# Hplc103.net
KiCad netlist of a schematic drawn in Altium Designer
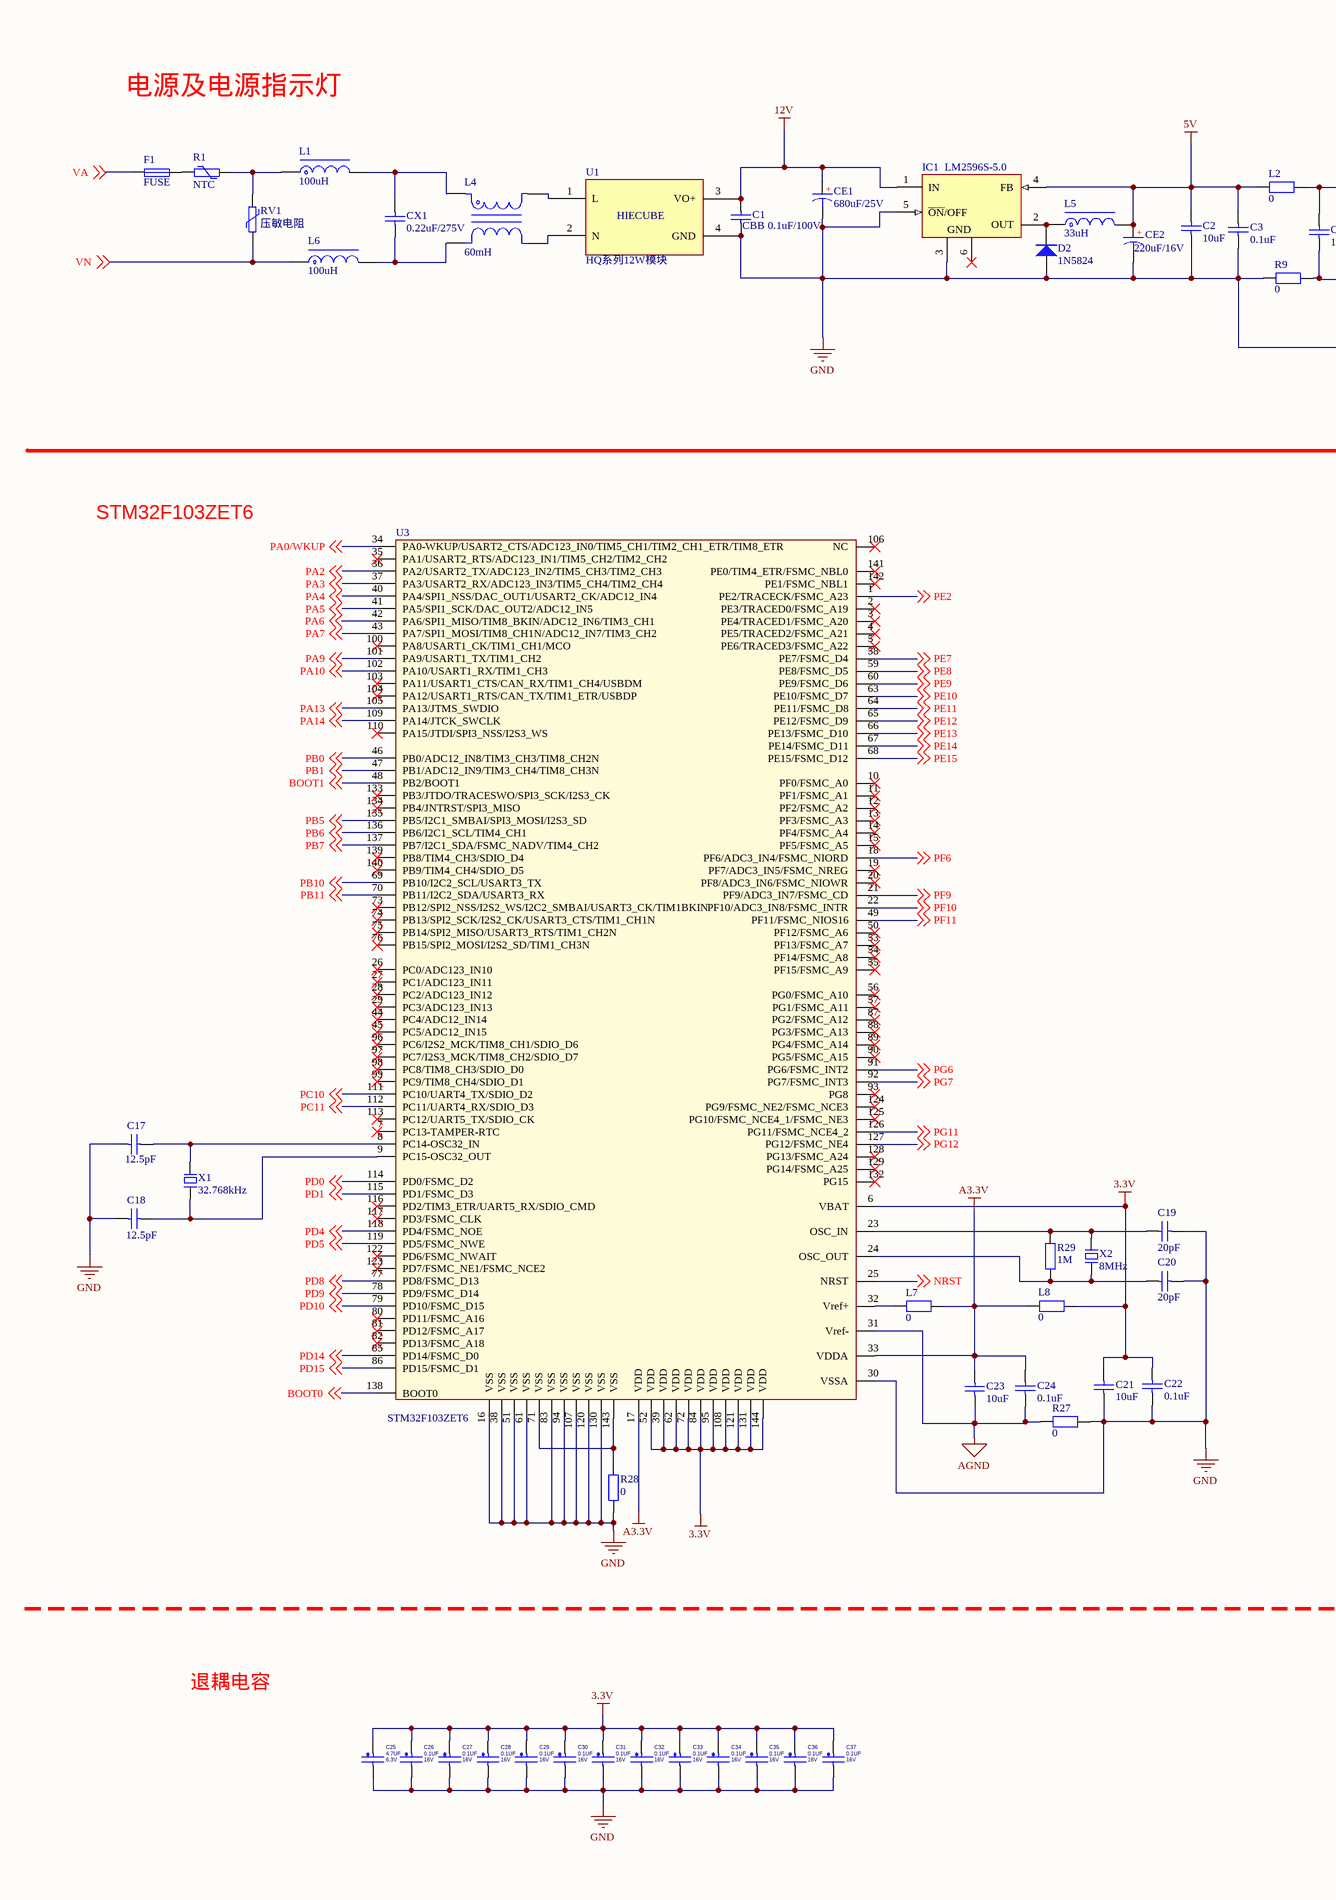
[diagram p0: Hplc103.SchDoc, left]
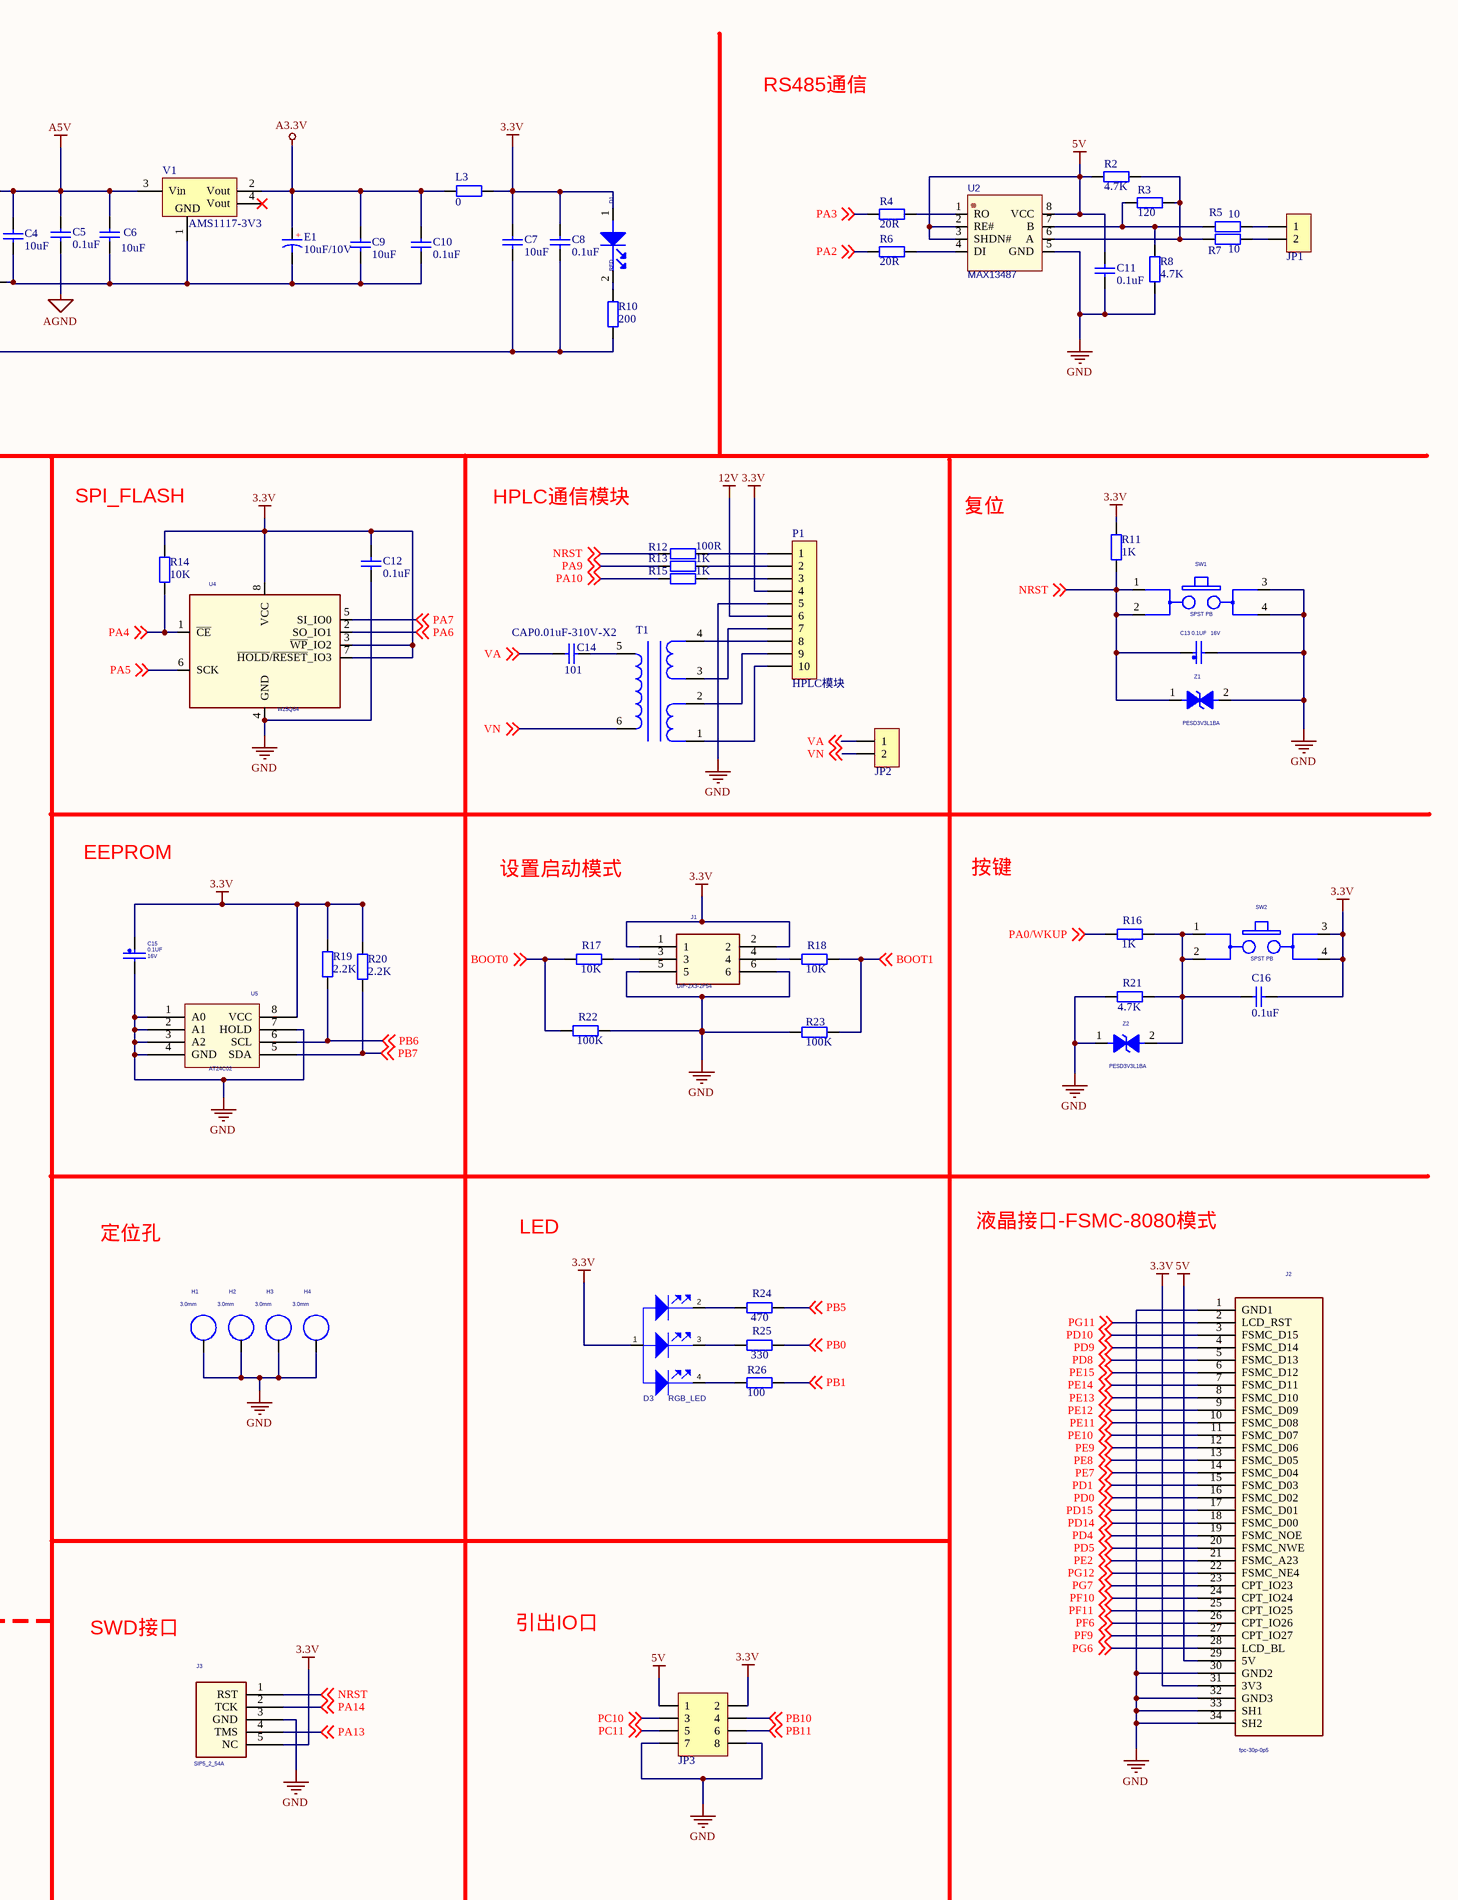
[diagram p1: Hplc103.SchDoc, right]

(export (version "E")
  (design (tool "Eeschema 10.0.6"))
  (components
    (comp (ref "C1")
      (value "CBB 0.1uF/100V")
      (footprint "CBB 5*6.3*3")
      (description "CBB电容")
      (libsource (lib "0.1 - 电阻-电容-电感-电位器") (part "CBB"))
    )
    (comp (ref "C2")
      (value "10uF")
      (footprint "C0805_M")
      (description "贴片电容")
      (libsource (lib "0.1 - 电阻-电容-电感-电位器") (part "C"))
    )
    (comp (ref "C3")
      (value "0.1uF")
      (footprint "C0805_M")
      (description "贴片电容")
      (libsource (lib "0.1 - 电阻-电容-电感-电位器") (part "C"))
    )
    (comp (ref "C4")
      (value "10uF")
      (footprint "C0805_M")
      (description "贴片电容")
      (libsource (lib "0.1 - 电阻-电容-电感-电位器") (part "C"))
    )
    (comp (ref "C5")
      (value "0.1uF")
      (footprint "C0805_M")
      (description "贴片电容")
      (libsource (lib "0.1 - 电阻-电容-电感-电位器") (part "C"))
    )
    (comp (ref "C6")
      (value "10uF")
      (footprint "C0805_M")
      (description "贴片电容")
      (libsource (lib "0.1 - 电阻-电容-电感-电位器") (part "C"))
    )
    (comp (ref "C7")
      (value "10uF")
      (footprint "C0805_M")
      (description "贴片电容")
      (libsource (lib "0.1 - 电阻-电容-电感-电位器") (part "C"))
    )
    (comp (ref "C8")
      (value "0.1uF")
      (footprint "C0805_M")
      (description "贴片电容")
      (libsource (lib "0.1 - 电阻-电容-电感-电位器") (part "C"))
    )
    (comp (ref "C9")
      (value "10uF")
      (footprint "C0805_M")
      (description "贴片电容")
      (libsource (lib "0.1 - 电阻-电容-电感-电位器") (part "C"))
    )
    (comp (ref "C10")
      (value "0.1uF")
      (footprint "C0805_M")
      (description "贴片电容")
      (libsource (lib "0.1 - 电阻-电容-电感-电位器") (part "C"))
    )
    (comp (ref "C11")
      (value "0.1uF")
      (footprint "C0805_M")
      (description "贴片电容")
      (libsource (lib "0.1 - 电阻-电容-电感-电位器") (part "C"))
    )
    (comp (ref "C12")
      (value "0.1uF")
      (footprint "C0805_M")
      (description "贴片电容")
      (libsource (lib "0.1 - 电阻-电容-电感-电位器") (part "C"))
    )
    (comp (ref "C13")
      (value "0.1UF")
      (description "CAP CER 22UF 6.3V 20% X5R 0603")
      (fields
        (field (name "TOLERANCE") "20%")
        (field (name "VOLTAGE") "6.3V")
        (field (name "VOLTAGE RATING") "16V")
      )
      (libsource (lib "Hplc103") (part "CAP_NP"))
    )
    (comp (ref "C14")
      (value "101")
      (footprint "CY 7.5*12*5")
      (fields (field (name "ALTIUM_UNNAMED_1") "CAP0.01uF-310V-X2"))
      (libsource (lib "Schlib1") (part "电容"))
    )
    (comp (ref "C15")
      (value "0.1UF")
      (description "CAP CER 22UF 6.3V 20% X5R 0402")
      (fields
        (field (name "TOLERANCE") "20%")
        (field (name "VOLTAGE") "6.3V")
        (field (name "VOLTAGE RATING") "16V")
      )
      (libsource (lib "Hplc103") (part "CAP_NP"))
    )
    (comp (ref "C16")
      (value "0.1uF")
      (footprint "C0805_M")
      (description "贴片电容")
      (libsource (lib "0.1 - 电阻-电容-电感-电位器") (part "C"))
    )
    (comp (ref "C17")
      (value "12.5pF")
      (footprint "C0805_M")
      (description "贴片电容")
      (libsource (lib "0.1 - 电阻-电容-电感-电位器") (part "C"))
    )
    (comp (ref "C18")
      (value "12.5pF")
      (footprint "C0805_M")
      (description "贴片电容")
      (libsource (lib "0.1 - 电阻-电容-电感-电位器") (part "C"))
    )
    (comp (ref "C19")
      (value "20pF")
      (footprint "C0805_M")
      (description "贴片电容")
      (libsource (lib "0.1 - 电阻-电容-电感-电位器") (part "C"))
    )
    (comp (ref "C20")
      (value "20pF")
      (footprint "C0805_M")
      (description "贴片电容")
      (libsource (lib "0.1 - 电阻-电容-电感-电位器") (part "C"))
    )
    (comp (ref "C21")
      (value "10uF")
      (footprint "C0805_M")
      (description "贴片电容")
      (libsource (lib "0.1 - 电阻-电容-电感-电位器") (part "C"))
    )
    (comp (ref "C22")
      (value "0.1uF")
      (footprint "C0805_M")
      (description "贴片电容")
      (libsource (lib "0.1 - 电阻-电容-电感-电位器") (part "C"))
    )
    (comp (ref "C23")
      (value "10uF")
      (footprint "C0805_M")
      (description "贴片电容")
      (libsource (lib "0.1 - 电阻-电容-电感-电位器") (part "C"))
    )
    (comp (ref "C24")
      (value "0.1uF")
      (footprint "C0805_M")
      (description "贴片电容")
      (libsource (lib "0.1 - 电阻-电容-电感-电位器") (part "C"))
    )
    (comp (ref "C25")
      (value "4.7UF")
      (footprint "C0603")
      (description "CAP CER 22UF 6.3V 20% X5R 0603")
      (fields
        (field (name "TOLERANCE") "20%")
        (field (name "VOLTAGE") "6.3V")
        (field (name "VOLTAGE RATING") "6.3V")
      )
      (libsource (lib "Hplc103") (part "CAP_NP"))
    )
    (comp (ref "C26")
      (value "0.1UF")
      (description "CAP CER 22UF 6.3V 20% X5R 0603")
      (fields
        (field (name "TOLERANCE") "20%")
        (field (name "VOLTAGE") "6.3V")
        (field (name "VOLTAGE RATING") "16V")
      )
      (libsource (lib "Hplc103") (part "CAP_NP"))
    )
    (comp (ref "C27")
      (value "0.1UF")
      (description "CAP CER 22UF 6.3V 20% X5R 0603")
      (fields
        (field (name "TOLERANCE") "20%")
        (field (name "VOLTAGE") "6.3V")
        (field (name "VOLTAGE RATING") "16V")
      )
      (libsource (lib "Hplc103") (part "CAP_NP"))
    )
    (comp (ref "C28")
      (value "0.1UF")
      (description "CAP CER 22UF 6.3V 20% X5R 0603")
      (fields
        (field (name "TOLERANCE") "20%")
        (field (name "VOLTAGE") "6.3V")
        (field (name "VOLTAGE RATING") "16V")
      )
      (libsource (lib "Hplc103") (part "CAP_NP"))
    )
    (comp (ref "C29")
      (value "0.1UF")
      (description "CAP CER 22UF 6.3V 20% X5R 0603")
      (fields
        (field (name "TOLERANCE") "20%")
        (field (name "VOLTAGE") "6.3V")
        (field (name "VOLTAGE RATING") "16V")
      )
      (libsource (lib "Hplc103") (part "CAP_NP"))
    )
    (comp (ref "C30")
      (value "0.1UF")
      (description "CAP CER 22UF 6.3V 20% X5R 0603")
      (fields
        (field (name "TOLERANCE") "20%")
        (field (name "VOLTAGE") "6.3V")
        (field (name "VOLTAGE RATING") "16V")
      )
      (libsource (lib "Hplc103") (part "CAP_NP"))
    )
    (comp (ref "C31")
      (value "0.1UF")
      (description "CAP CER 22UF 6.3V 20% X5R 0603")
      (fields
        (field (name "TOLERANCE") "20%")
        (field (name "VOLTAGE") "6.3V")
        (field (name "VOLTAGE RATING") "16V")
      )
      (libsource (lib "Hplc103") (part "CAP_NP"))
    )
    (comp (ref "C32")
      (value "0.1UF")
      (description "CAP CER 22UF 6.3V 20% X5R 0603")
      (fields
        (field (name "TOLERANCE") "20%")
        (field (name "VOLTAGE") "6.3V")
        (field (name "VOLTAGE RATING") "16V")
      )
      (libsource (lib "Hplc103") (part "CAP_NP"))
    )
    (comp (ref "C33")
      (value "0.1UF")
      (description "CAP CER 22UF 6.3V 20% X5R 0603")
      (fields
        (field (name "TOLERANCE") "20%")
        (field (name "VOLTAGE") "6.3V")
        (field (name "VOLTAGE RATING") "16V")
      )
      (libsource (lib "Hplc103") (part "CAP_NP"))
    )
    (comp (ref "C34")
      (value "0.1UF")
      (description "CAP CER 22UF 6.3V 20% X5R 0603")
      (fields
        (field (name "TOLERANCE") "20%")
        (field (name "VOLTAGE") "6.3V")
        (field (name "VOLTAGE RATING") "16V")
      )
      (libsource (lib "Hplc103") (part "CAP_NP"))
    )
    (comp (ref "C35")
      (value "0.1UF")
      (description "CAP CER 22UF 6.3V 20% X5R 0603")
      (fields
        (field (name "TOLERANCE") "20%")
        (field (name "VOLTAGE") "6.3V")
        (field (name "VOLTAGE RATING") "16V")
      )
      (libsource (lib "Hplc103") (part "CAP_NP"))
    )
    (comp (ref "C36")
      (value "0.1UF")
      (description "CAP CER 22UF 6.3V 20% X5R 0603")
      (fields
        (field (name "TOLERANCE") "20%")
        (field (name "VOLTAGE") "6.3V")
        (field (name "VOLTAGE RATING") "16V")
      )
      (libsource (lib "Hplc103") (part "CAP_NP"))
    )
    (comp (ref "C37")
      (value "0.1UF")
      (description "CAP CER 22UF 6.3V 20% X5R 0603")
      (fields
        (field (name "TOLERANCE") "20%")
        (field (name "VOLTAGE") "6.3V")
        (field (name "VOLTAGE RATING") "16V")
      )
      (libsource (lib "Hplc103") (part "CAP_NP"))
    )
    (comp (ref "CE1")
      (value "680uF/25V")
      (footprint "CAP 5.0*10*16 - GD")
      (description "直插电解电容")
      (libsource (lib "0.1 - 电阻-电容-电感-电位器") (part "CE"))
    )
    (comp (ref "CE2")
      (value "220uF/16V")
      (footprint "CAP 2.5*6.3*7")
      (description "直插电解电容")
      (libsource (lib "0.1 - 电阻-电容-电感-电位器") (part "CE"))
    )
    (comp (ref "CX1")
      (value "0.22uF/275V")
      (footprint "CX 10*13*11")
      (description "安规X电容")
      (libsource (lib "0.1 - 电阻-电容-电感-电位器") (part "CX"))
    )
    (comp (ref "D1") (value "RED") (libsource (lib "Hplc103") (part "LED_0")))
    (comp (ref "D2")
      (value "1N5824")
      (footprint "SMA")
      (description "肖特基二极管")
      (libsource (lib "0.2 - 二极管-TVS-整流桥") (part "1N5822"))
    )
    (comp (ref "D3")
      (value "RGB_LED")
      (footprint "LED_RGB_5MM")
      (description "LED GRN SGL 25MA 0603")
      (fields (field (name "Comment") "LED_1"))
      (libsource (lib "Hplc103") (part "LED_1"))
    )
    (comp (ref "E1")
      (value "10uF/10V")
      (footprint "C_3216")
      (description "贴片钽电容")
      (libsource (lib "0.1 - 电阻-电容-电感-电位器") (part "CT"))
    )
    (comp (ref "F1") (value "FUSE") (footprint "FUSE") (libsource (lib "DEMO板原理图封装") (part "FUSE")))
    (comp (ref "H1")
      (value "3.0mm")
      (description "FASTENER, STANDOFF 4.5MMX3.53XM3.0X0.5 ROUND THR .635\"L BRASS")
      (libsource (lib "Hplc103") (part "SPACER_0"))
    )
    (comp (ref "H2")
      (value "3.0mm")
      (description "FASTENER, STANDOFF 4.5MMX3.53XM3.0X0.5 ROUND THR .635\"L BRASS")
      (libsource (lib "Hplc103") (part "SPACER_0"))
    )
    (comp (ref "H3")
      (value "3.0mm")
      (description "FASTENER, STANDOFF 4.5MMX3.53XM3.0X0.5 ROUND THR .635\"L BRASS")
      (libsource (lib "Hplc103") (part "SPACER_0"))
    )
    (comp (ref "H4")
      (value "3.0mm")
      (description "FASTENER, STANDOFF 4.5MMX3.53XM3.0X0.5 ROUND THR .635\"L BRASS")
      (libsource (lib "Hplc103") (part "SPACER_0"))
    )
    (comp (ref "IC1")
      (value "LM2596S-5.0")
      (footprint "TO263-5A")
      (description "3A DC-DC降压芯片")
      (libsource (lib "1.1 - 电源类芯片") (part "LM2596S"))
    )
    (comp (ref "J1") (value "DIP-2X3-2P54") (libsource (lib "Hplc103") (part "2X4_2")))
    (comp (ref "J2") (value "fpc-30p-0p5") (libsource (lib "Hplc103") (part "CON30_2")))
    (comp (ref "J3") (value "SIP5_2_54A") (libsource (lib "Hplc103") (part "SIP5_2_0")))
    (comp (ref "JP1")
      (value "HDR-1X2")
      (footprint "KF128-3.81-2P")
      (description "2P接插件")
      (libsource (lib "Hplc103") (part "Header 2"))
    )
    (comp (ref "JP2")
      (value "HDR-1X2")
      (footprint "2EHDVC")
      (description "2P接插件")
      (libsource (lib "6.1 - 接插件-脚距5.08 (200mil) ") (part "Header 2"))
    )
    (comp (ref "JP3")
      (value "Header 4X2")
      (footprint "CON20VP2R54-2X4TM")
      (description "4*2P接插件")
      (fields (field (name "版权归属") "源创客"))
      (libsource (lib "接插件") (part "Header 4X2"))
    )
    (comp (ref "L1")
      (value "100uH")
      (footprint "CD54")
      (description "CD系列贴片线绕功率电感")
      (libsource (lib "0.1 - 电阻-电容-电感-电位器") (part "L-SMD"))
    )
    (comp (ref "L2")
      (value "0")
      (footprint "R0603")
      (description "贴片电阻")
      (libsource (lib "0.1 - 电阻-电容-电感-电位器") (part "R"))
    )
    (comp (ref "L3")
      (value "0")
      (footprint "R0603")
      (description "贴片电阻")
      (libsource (lib "0.1 - 电阻-电容-电感-电位器") (part "R"))
    )
    (comp (ref "L4")
      (value "60mH")
      (footprint "UU9.8")
      (description "共模电感")
      (libsource (lib "0.1 - 电阻-电容-电感-电位器") (part "L-UU"))
    )
    (comp (ref "L5")
      (value "33uH")
      (footprint "CDRH127")
      (description "CDRH功率屏蔽电感")
      (libsource (lib "0.1 - 电阻-电容-电感-电位器") (part "L-CDRH"))
    )
    (comp (ref "L6")
      (value "100uH")
      (footprint "CD54")
      (description "CD系列贴片线绕功率电感")
      (libsource (lib "0.1 - 电阻-电容-电感-电位器") (part "L-SMD"))
    )
    (comp (ref "L7")
      (value "0")
      (footprint "R0603")
      (description "贴片电阻")
      (libsource (lib "0.1 - 电阻-电容-电感-电位器") (part "R"))
    )
    (comp (ref "L8")
      (value "0")
      (footprint "R0603")
      (description "贴片电阻")
      (libsource (lib "0.1 - 电阻-电容-电感-电位器") (part "R"))
    )
    (comp (ref "P1")
      (value "HPLC模块")
      (footprint "HDR2.0-M-LI-10P")
      (libsource (lib "Schlib1") (part "pin1*10（小）"))
    )
    (comp (ref "R1") (value "NTC") (footprint "NTC") (libsource (lib "DEMO板原理图封装") (part "NTC")))
    (comp (ref "R2") (value "4.7K") (footprint "R0805_M") (libsource (lib "") (part "Res_1_3")))
    (comp (ref "R3") (value "120") (footprint "R0805_M") (libsource (lib "") (part "Res_1_3")))
    (comp (ref "R4") (value "20R") (footprint "R0805_M") (libsource (lib "Hplc103") (part "Res_1")))
    (comp (ref "R5") (value "10") (footprint "R0805_M") (libsource (lib "Hplc103") (part "Res_1")))
    (comp (ref "R6") (value "20R") (footprint "R0805_M") (libsource (lib "Hplc103") (part "Res_1")))
    (comp (ref "R7") (value "10") (footprint "R0805_M") (libsource (lib "Hplc103") (part "Res_1")))
    (comp (ref "R8") (value "4.7K") (footprint "R0805_M") (libsource (lib "") (part "Res_1_1")))
    (comp (ref "R9")
      (value "0")
      (footprint "R0603")
      (description "贴片电阻")
      (libsource (lib "0.1 - 电阻-电容-电感-电位器") (part "R"))
    )
    (comp (ref "R10") (value "200") (footprint "R0805_M") (libsource (lib "") (part "Res_1_1")))
    (comp (ref "R11") (value "1K") (footprint "R0805_M") (libsource (lib "") (part "Res_1_1")))
    (comp (ref "R12")
      (value "100R")
      (footprint "R0805_M")
      (fields (field (name "ALTIUM_UNNAMED_1") "100R"))
      (libsource (lib "Schlib1") (part "电阻"))
    )
    (comp (ref "R13")
      (value "1K")
      (footprint "R0805_M")
      (fields (field (name "ALTIUM_UNNAMED_1") "1K"))
      (libsource (lib "Schlib1") (part "电阻"))
    )
    (comp (ref "R14") (value "10K") (footprint "R0805_M") (libsource (lib "") (part "Res_1_2")))
    (comp (ref "R15")
      (value "1K")
      (footprint "R0805_M")
      (fields (field (name "ALTIUM_UNNAMED_1") "1K"))
      (libsource (lib "Schlib1") (part "电阻"))
    )
    (comp (ref "R16") (value "1K") (footprint "R0805_M") (libsource (lib "Hplc103") (part "Res_1")))
    (comp (ref "R17") (value "10K") (footprint "R0805_M") (libsource (lib "Hplc103") (part "Res_1")))
    (comp (ref "R18") (value "10K") (footprint "R0805_M") (libsource (lib "Hplc103") (part "Res_1")))
    (comp (ref "R19") (value "2.2K") (footprint "R0805_M") (libsource (lib "") (part "Res_1_2")))
    (comp (ref "R20") (value "2.2K") (footprint "R0805_M") (libsource (lib "") (part "Res_1_2")))
    (comp (ref "R21") (value "4.7K") (footprint "R0805_M") (libsource (lib "Hplc103") (part "Res_1")))
    (comp (ref "R22") (value "100K") (footprint "R0805_M") (libsource (lib "Hplc103") (part "Res_1")))
    (comp (ref "R23") (value "100K") (footprint "R0805_M") (libsource (lib "Hplc103") (part "Res_1")))
    (comp (ref "R24") (value "470") (footprint "R0805_M") (libsource (lib "Hplc103") (part "Res_1")))
    (comp (ref "R25") (value "330") (footprint "R0805_M") (libsource (lib "Hplc103") (part "Res_1")))
    (comp (ref "R26") (value "100") (footprint "R0805_M") (libsource (lib "") (part "Res_1_3")))
    (comp (ref "R27")
      (value "0")
      (footprint "R0603")
      (description "贴片电阻")
      (libsource (lib "0.1 - 电阻-电容-电感-电位器") (part "R"))
    )
    (comp (ref "R28")
      (value "0")
      (footprint "R0603")
      (description "贴片电阻")
      (libsource (lib "0.1 - 电阻-电容-电感-电位器") (part "R"))
    )
    (comp (ref "R29")
      (value "1M")
      (footprint "R0805_M")
      (description "贴片电阻")
      (libsource (lib "0.1 - 电阻-电容-电感-电位器") (part "R"))
    )
    (comp (ref "RV1") (value "压敏电阻") (footprint "TVR-14D") (libsource (lib "DEMO板原理图封装") (part "压敏电阻")))
    (comp (ref "SW1")
      (value "SPST PB")
      (description "SW SPST MOM NO PB TACT 50mA 50V SMT")
      (libsource (lib "Hplc103") (part "SW_PB_ESW_0"))
    )
    (comp (ref "SW2")
      (value "SPST PB")
      (description "SW SPST MOM NO PB TACT 50mA 50V SMT")
      (libsource (lib "Hplc103") (part "SW_PB_ESW_0"))
    )
    (comp (ref "T1")
      (value "EPC17-5V")
      (footprint "HDR2&4")
      (description "12V 高频变压器")
      (fields (field (name "版权归属") "源创客"))
      (libsource (lib "12.1 - 变压器") (part "EPC17-5V"))
    )
    (comp (ref "U1")
      (value "HQ系列12W模块")
      (footprint "12W单输出模块")
      (libsource (lib "DEMO板原理图封装") (part "HQ系列12W模块"))
    )
    (comp (ref "U2")
      (value "MAX13487")
      (footprint "SOIC-8")
      (fields (field (name "BOM_MANUFACTURER PART") "MAX13487EESA"))
      (libsource (lib "Hplc103") (part "MAX13487"))
    )
    (comp (ref "U3")
      (value "STM32F103ZET6")
      (footprint "LQFP144-050")
      (libsource (lib "Hplc103") (part "STM32F103ZET6"))
    )
    (comp (ref "U4")
      (value "W25Q64")
      (description "IC MEM FLASH QPI 64Mb 1.65-1.95V SOIC8W")
      (libsource (lib "Hplc103") (part "25WP_2"))
    )
    (comp (ref "U5") (value "AT24C02") (libsource (lib "Hplc103") (part "AT24C02_0")))
    (comp (ref "V1")
      (value "AMS1117-3V3")
      (footprint "SOT223_M")
      (description "三端稳压芯片")
      (libsource (lib "1.1 - 电源类芯片") (part "AMS1117"))
    )
    (comp (ref "X1")
      (value "32.768kHz")
      (footprint "OSC 3215-2P")
      (description "2脚无源脚晶振")
      (libsource (lib "0.5 - 保险丝-晶振-光耦") (part "XTAL-2P"))
    )
    (comp (ref "X2")
      (value "8MHz")
      (footprint "OSC 5032-2P")
      (description "2脚无源脚晶振")
      (libsource (lib "0.5 - 保险丝-晶振-光耦") (part "XTAL-2P"))
    )
    (comp (ref "Z1") (value "PESD3V3L1BA") (libsource (lib "Hplc103") (part "DIODE BI-DIR TRIG")))
    (comp (ref "Z2") (value "PESD3V3L1BA") (libsource (lib "Hplc103") (part "DIODE BI-DIR TRIG")))
  )
  (nets
    (net (code "1") (name "3.3V") (class "Default")
      (node (ref "C12") (pin "1") (pinfunction "1_1") (pintype "passive"))
      (node (ref "C15") (pin "1") (pinfunction "1_1") (pintype "passive"))
      (node (ref "C16") (pin "2") (pinfunction "2_2") (pintype "passive"))
      (node (ref "C21") (pin "2") (pinfunction "2_2") (pintype "passive"))
      (node (ref "C22") (pin "2") (pinfunction "2_2") (pintype "passive"))
      (node (ref "C25") (pin "1") (pinfunction "1_1") (pintype "passive"))
      (node (ref "C26") (pin "1") (pinfunction "1_1") (pintype "passive"))
      (node (ref "C27") (pin "1") (pinfunction "1_1") (pintype "passive"))
      (node (ref "C28") (pin "1") (pinfunction "1_1") (pintype "passive"))
      (node (ref "C29") (pin "1") (pinfunction "1_1") (pintype "passive"))
      (node (ref "C30") (pin "1") (pinfunction "1_1") (pintype "passive"))
      (node (ref "C31") (pin "1") (pinfunction "1_1") (pintype "passive"))
      (node (ref "C32") (pin "1") (pinfunction "1_1") (pintype "passive"))
      (node (ref "C33") (pin "1") (pinfunction "1_1") (pintype "passive"))
      (node (ref "C34") (pin "1") (pinfunction "1_1") (pintype "passive"))
      (node (ref "C35") (pin "1") (pinfunction "1_1") (pintype "passive"))
      (node (ref "C36") (pin "1") (pinfunction "1_1") (pintype "passive"))
      (node (ref "C37") (pin "1") (pinfunction "1_1") (pintype "passive"))
      (node (ref "C7") (pin "2") (pinfunction "2_2") (pintype "passive"))
      (node (ref "C8") (pin "2") (pinfunction "2_2") (pintype "passive"))
      (node (ref "D1") (pin "1") (pinfunction "ANODE_1") (pintype "passive"))
      (node (ref "D3") (pin "1") (pinfunction "ANODE_1") (pintype "passive"))
      (node (ref "J1") (pin "1") (pinfunction "1_1") (pintype "passive"))
      (node (ref "J1") (pin "2") (pinfunction "2_2") (pintype "passive"))
      (node (ref "J2") (pin "31") (pinfunction "3V3_31") (pintype "passive"))
      (node (ref "J3") (pin "5") (pinfunction "NC_5") (pintype "passive"))
      (node (ref "JP3") (pin "2") (pinfunction "2_2") (pintype "passive"))
      (node (ref "L3") (pin "1") (pinfunction "1_1") (pintype "passive"))
      (node (ref "L8") (pin "1") (pinfunction "1_1") (pintype "passive"))
      (node (ref "P1") (pin "4") (pinfunction "4_4") (pintype "power_in"))
      (node (ref "R11") (pin "2") (pinfunction "2_2") (pintype "passive"))
      (node (ref "R14") (pin "1") (pinfunction "1_1") (pintype "passive"))
      (node (ref "R19") (pin "1") (pinfunction "1_1") (pintype "passive"))
      (node (ref "R20") (pin "1") (pinfunction "1_1") (pintype "passive"))
      (node (ref "SW2") (pin "3") (pinfunction "B1_3") (pintype "passive"))
      (node (ref "SW2") (pin "4") (pinfunction "B2_4") (pintype "passive"))
      (node (ref "U3") (pin "108") (pinfunction "VDD_108") (pintype "passive"))
      (node (ref "U3") (pin "121") (pinfunction "VDD_121") (pintype "passive"))
      (node (ref "U3") (pin "131") (pinfunction "VDD_131") (pintype "passive"))
      (node (ref "U3") (pin "144") (pinfunction "VDD_144") (pintype "passive"))
      (node (ref "U3") (pin "39") (pinfunction "VDD_39") (pintype "passive"))
      (node (ref "U3") (pin "52") (pinfunction "VDD_52") (pintype "passive"))
      (node (ref "U3") (pin "6") (pinfunction "VBAT_6") (pintype "passive"))
      (node (ref "U3") (pin "62") (pinfunction "VDD_62") (pintype "passive"))
      (node (ref "U3") (pin "72") (pinfunction "VDD_72") (pintype "passive"))
      (node (ref "U3") (pin "84") (pinfunction "VDD_84") (pintype "passive"))
      (node (ref "U3") (pin "95") (pinfunction "VDD_95") (pintype "passive"))
      (node (ref "U4") (pin "3") (pinfunction "~{WP}_IO2_3") (pintype "passive"))
      (node (ref "U4") (pin "7") (pinfunction "~{HOLD}/~{RESET}_IO3_7") (pintype "passive"))
      (node (ref "U4") (pin "8") (pinfunction "VCC_8") (pintype "power_in"))
      (node (ref "U5") (pin "8") (pinfunction "VCC_8") (pintype "passive"))
    )
    (net (code "2") (name "5V") (class "Default")
      (node (ref "C11") (pin "1") (pinfunction "1_1") (pintype "passive"))
      (node (ref "C2") (pin "2") (pinfunction "2_2") (pintype "passive"))
      (node (ref "C3") (pin "2") (pinfunction "2_2") (pintype "passive"))
      (node (ref "CE2") (pin "1") (pinfunction "1_1") (pintype "passive"))
      (node (ref "IC1") (pin "4") (pinfunction "FB_4") (pintype "input"))
      (node (ref "J2") (pin "29") (pinfunction "5V_29") (pintype "passive"))
      (node (ref "JP3") (pin "1") (pinfunction "1_1") (pintype "passive"))
      (node (ref "L2") (pin "2") (pinfunction "2_2") (pintype "passive"))
      (node (ref "L5") (pin "2") (pinfunction "2_2") (pintype "passive"))
      (node (ref "R2") (pin "2") (pinfunction "2_2") (pintype "passive"))
      (node (ref "U2") (pin "2") (pinfunction "RE#_2") (pintype "passive"))
      (node (ref "U2") (pin "3") (pinfunction "SHDN#_3") (pintype "passive"))
      (node (ref "U2") (pin "8") (pinfunction "VCC_8") (pintype "passive"))
    )
    (net (code "3") (name "12V") (class "Default")
      (node (ref "C1") (pin "1") (pinfunction "1_1") (pintype "passive"))
      (node (ref "CE1") (pin "1") (pinfunction "1_1") (pintype "passive"))
      (node (ref "IC1") (pin "1") (pinfunction "IN_1") (pintype "power_in"))
      (node (ref "P1") (pin "6") (pinfunction "6_6") (pintype "power_in"))
      (node (ref "U1") (pin "3") (pinfunction "VO+_3") (pintype "passive"))
    )
    (net (code "4") (name "A3.3V") (class "Default")
      (node (ref "C10") (pin "2") (pinfunction "2_2") (pintype "passive"))
      (node (ref "C23") (pin "2") (pinfunction "2_2") (pintype "passive"))
      (node (ref "C24") (pin "2") (pinfunction "2_2") (pintype "passive"))
      (node (ref "C9") (pin "2") (pinfunction "2_2") (pintype "passive"))
      (node (ref "E1") (pin "1") (pinfunction "A_1") (pintype "passive"))
      (node (ref "L3") (pin "2") (pinfunction "2_2") (pintype "passive"))
      (node (ref "L7") (pin "1") (pinfunction "1_1") (pintype "passive"))
      (node (ref "L8") (pin "2") (pinfunction "2_2") (pintype "passive"))
      (node (ref "U3") (pin "17") (pinfunction "VDD_17") (pintype "passive"))
      (node (ref "U3") (pin "33") (pinfunction "VDDA_33") (pintype "passive"))
      (node (ref "V1") (pin "2") (pinfunction "Vout_2") (pintype "passive"))
    )
    (net (code "5") (name "A5V") (class "Default")
      (node (ref "C4") (pin "2") (pinfunction "2_2") (pintype "passive"))
      (node (ref "C5") (pin "2") (pinfunction "2_2") (pintype "passive"))
      (node (ref "C6") (pin "1") (pinfunction "1_1") (pintype "passive"))
      (node (ref "L2") (pin "1") (pinfunction "1_1") (pintype "passive"))
      (node (ref "V1") (pin "3") (pinfunction "Vin_3") (pintype "passive"))
    )
    (net (code "6") (name "AGND") (class "Default")
      (node (ref "C23") (pin "1") (pinfunction "1_1") (pintype "passive"))
      (node (ref "C24") (pin "1") (pinfunction "1_1") (pintype "passive"))
      (node (ref "C5") (pin "1") (pinfunction "1_1") (pintype "passive"))
      (node (ref "R27") (pin "1") (pinfunction "1_1") (pintype "passive"))
      (node (ref "U3") (pin "31") (pinfunction "Vref-_31") (pintype "passive"))
    )
    (net (code "7") (name "BOOT0") (class "Default")
      (node (ref "R17") (pin "1") (pinfunction "1_1") (pintype "passive"))
      (node (ref "R22") (pin "1") (pinfunction "1_1") (pintype "passive"))
      (node (ref "U3") (pin "138") (pinfunction "BOOT0_138") (pintype "passive"))
    )
    (net (code "8") (name "BOOT1") (class "Default")
      (node (ref "R18") (pin "2") (pinfunction "2_2") (pintype "passive"))
      (node (ref "R23") (pin "2") (pinfunction "2_2") (pintype "passive"))
      (node (ref "U3") (pin "48") (pinfunction "PB2/BOOT1_48") (pintype "passive"))
    )
    (net (code "9") (name "GND") (class "Default")
      (node (ref "C1") (pin "2") (pinfunction "2_2") (pintype "passive"))
      (node (ref "C11") (pin "2") (pinfunction "2_2") (pintype "passive"))
      (node (ref "C12") (pin "2") (pinfunction "2_2") (pintype "passive"))
      (node (ref "C13") (pin "2") (pinfunction "2_2") (pintype "passive"))
      (node (ref "C15") (pin "2") (pinfunction "2_2") (pintype "passive"))
      (node (ref "C17") (pin "1") (pinfunction "1_1") (pintype "passive"))
      (node (ref "C18") (pin "1") (pinfunction "1_1") (pintype "passive"))
      (node (ref "C19") (pin "1") (pinfunction "1_1") (pintype "passive"))
      (node (ref "C2") (pin "1") (pinfunction "1_1") (pintype "passive"))
      (node (ref "C20") (pin "1") (pinfunction "1_1") (pintype "passive"))
      (node (ref "C21") (pin "1") (pinfunction "1_1") (pintype "passive"))
      (node (ref "C22") (pin "1") (pinfunction "1_1") (pintype "passive"))
      (node (ref "C25") (pin "2") (pinfunction "2_2") (pintype "passive"))
      (node (ref "C26") (pin "2") (pinfunction "2_2") (pintype "passive"))
      (node (ref "C27") (pin "2") (pinfunction "2_2") (pintype "passive"))
      (node (ref "C28") (pin "2") (pinfunction "2_2") (pintype "passive"))
      (node (ref "C29") (pin "2") (pinfunction "2_2") (pintype "passive"))
      (node (ref "C3") (pin "1") (pinfunction "1_1") (pintype "passive"))
      (node (ref "C30") (pin "2") (pinfunction "2_2") (pintype "passive"))
      (node (ref "C31") (pin "2") (pinfunction "2_2") (pintype "passive"))
      (node (ref "C32") (pin "2") (pinfunction "2_2") (pintype "passive"))
      (node (ref "C33") (pin "2") (pinfunction "2_2") (pintype "passive"))
      (node (ref "C34") (pin "2") (pinfunction "2_2") (pintype "passive"))
      (node (ref "C35") (pin "2") (pinfunction "2_2") (pintype "passive"))
      (node (ref "C36") (pin "2") (pinfunction "2_2") (pintype "passive"))
      (node (ref "C37") (pin "2") (pinfunction "2_2") (pintype "passive"))
      (node (ref "C7") (pin "1") (pinfunction "1_1") (pintype "passive"))
      (node (ref "C8") (pin "1") (pinfunction "1_1") (pintype "passive"))
      (node (ref "CE1") (pin "2") (pinfunction "2_2") (pintype "passive"))
      (node (ref "CE2") (pin "2") (pinfunction "2_2") (pintype "passive"))
      (node (ref "D2") (pin "1") (pinfunction "A_1") (pintype "passive"))
      (node (ref "H1") (pin "1") (pinfunction "NC_1_1") (pintype "passive"))
      (node (ref "H2") (pin "1") (pinfunction "NC_1_1") (pintype "passive"))
      (node (ref "H3") (pin "1") (pinfunction "NC_1_1") (pintype "passive"))
      (node (ref "H4") (pin "1") (pinfunction "NC_1_1") (pintype "passive"))
      (node (ref "IC1") (pin "3") (pinfunction "GND_3") (pintype "power_in"))
      (node (ref "IC1") (pin "5") (pinfunction "~{ON}/OFF_5") (pintype "input"))
      (node (ref "J1") (pin "5") (pinfunction "5_5") (pintype "passive"))
      (node (ref "J1") (pin "6") (pinfunction "6_6") (pintype "passive"))
      (node (ref "J2") (pin "1") (pinfunction "GND1_1") (pintype "passive"))
      (node (ref "J2") (pin "30") (pinfunction "GND2_30") (pintype "passive"))
      (node (ref "J2") (pin "32") (pinfunction "GND3_32") (pintype "passive"))
      (node (ref "J2") (pin "33") (pinfunction "SH1_33") (pintype "passive"))
      (node (ref "J2") (pin "34") (pinfunction "SH2_34") (pintype "passive"))
      (node (ref "J3") (pin "3") (pinfunction "GND_3") (pintype "passive"))
      (node (ref "JP3") (pin "7") (pinfunction "7_7") (pintype "passive"))
      (node (ref "JP3") (pin "8") (pinfunction "8_8") (pintype "passive"))
      (node (ref "P1") (pin "5") (pinfunction "5_5") (pintype "power_in"))
      (node (ref "R10") (pin "1") (pinfunction "1_1") (pintype "passive"))
      (node (ref "R21") (pin "1") (pinfunction "1_1") (pintype "passive"))
      (node (ref "R22") (pin "2") (pinfunction "2_2") (pintype "passive"))
      (node (ref "R23") (pin "1") (pinfunction "1_1") (pintype "passive"))
      (node (ref "R27") (pin "2") (pinfunction "2_2") (pintype "passive"))
      (node (ref "R28") (pin "2") (pinfunction "2_2") (pintype "passive"))
      (node (ref "R8") (pin "1") (pinfunction "1_1") (pintype "passive"))
      (node (ref "R9") (pin "2") (pinfunction "2_2") (pintype "passive"))
      (node (ref "SW1") (pin "3") (pinfunction "B1_3") (pintype "passive"))
      (node (ref "SW1") (pin "4") (pinfunction "B2_4") (pintype "passive"))
      (node (ref "U1") (pin "4") (pinfunction "GND_4") (pintype "passive"))
      (node (ref "U2") (pin "5") (pinfunction "GND_5") (pintype "passive"))
      (node (ref "U3") (pin "107") (pinfunction "VSS_107") (pintype "passive"))
      (node (ref "U3") (pin "120") (pinfunction "VSS_120") (pintype "passive"))
      (node (ref "U3") (pin "130") (pinfunction "VSS_130") (pintype "passive"))
      (node (ref "U3") (pin "16") (pinfunction "VSS_16") (pintype "passive"))
      (node (ref "U3") (pin "30") (pinfunction "VSSA_30") (pintype "passive"))
      (node (ref "U3") (pin "38") (pinfunction "VSS_38") (pintype "passive"))
      (node (ref "U3") (pin "51") (pinfunction "VSS_51") (pintype "passive"))
      (node (ref "U3") (pin "61") (pinfunction "VSS_61") (pintype "passive"))
      (node (ref "U3") (pin "83") (pinfunction "VSS_83") (pintype "passive"))
      (node (ref "U3") (pin "94") (pinfunction "VSS_94") (pintype "passive"))
      (node (ref "U4") (pin "4") (pinfunction "GND_4") (pintype "power_in"))
      (node (ref "U5") (pin "1") (pinfunction "A0_1") (pintype "passive"))
      (node (ref "U5") (pin "2") (pinfunction "A1_2") (pintype "passive"))
      (node (ref "U5") (pin "3") (pinfunction "A2_3") (pintype "passive"))
      (node (ref "U5") (pin "4") (pinfunction "GND_4") (pintype "passive"))
      (node (ref "U5") (pin "7") (pinfunction "HOLD_7") (pintype "passive"))
      (node (ref "Z1") (pin "2") (pinfunction "2_2") (pintype "passive"))
      (node (ref "Z2") (pin "1") (pinfunction "1_1") (pintype "passive"))
    )
    (net (code "10") (name "NRST") (class "Default")
      (node (ref "C13") (pin "1") (pinfunction "1_1") (pintype "passive"))
      (node (ref "J3") (pin "1") (pinfunction "RST_1") (pintype "passive"))
      (node (ref "R11") (pin "1") (pinfunction "1_1") (pintype "passive"))
      (node (ref "R12") (pin "1") (pinfunction "1_1") (pintype "passive"))
      (node (ref "SW1") (pin "1") (pinfunction "A1_1") (pintype "passive"))
      (node (ref "SW1") (pin "2") (pinfunction "A2_2") (pintype "passive"))
      (node (ref "U3") (pin "25") (pinfunction "NRST_25") (pintype "passive"))
      (node (ref "Z1") (pin "1") (pinfunction "1_1") (pintype "passive"))
    )
    (net (code "11") (name "Net-(C14-Pad2)") (class "Default")
      (node (ref "C14") (pin "2") (pinfunction "2_2") (pintype "passive"))
      (node (ref "T1") (pin "5") (pinfunction "5_5") (pintype "passive"))
    )
    (net (code "12") (name "Net-(CX1-Pad1)") (class "Default")
      (node (ref "CX1") (pin "1") (pinfunction "1_1") (pintype "passive"))
      (node (ref "L4") (pin "4") (pinfunction "4_4") (pintype "passive"))
      (node (ref "L6") (pin "2") (pinfunction "2_2") (pintype "passive"))
    )
    (net (code "13") (name "Net-(CX1-Pad2)") (class "Default")
      (node (ref "CX1") (pin "2") (pinfunction "2_2") (pintype "passive"))
      (node (ref "L1") (pin "2") (pinfunction "2_2") (pintype "passive"))
      (node (ref "L4") (pin "1") (pinfunction "1_1") (pintype "passive"))
    )
    (net (code "14") (name "Net-(D1-CATHODE)") (class "Default")
      (node (ref "D1") (pin "2") (pinfunction "CATHODE_2") (pintype "passive"))
      (node (ref "R10") (pin "2") (pinfunction "2_2") (pintype "passive"))
    )
    (net (code "15") (name "Net-(D2-K)") (class "Default")
      (node (ref "D2") (pin "2") (pinfunction "K_2") (pintype "passive"))
      (node (ref "IC1") (pin "2") (pinfunction "OUT_2") (pintype "power_in"))
      (node (ref "L5") (pin "1") (pinfunction "1_1") (pintype "passive"))
    )
    (net (code "16") (name "Net-(D3-B)") (class "Default")
      (node (ref "D3") (pin "4") (pinfunction "B_4") (pintype "passive"))
      (node (ref "R26") (pin "2") (pinfunction "2_2") (pintype "passive"))
    )
    (net (code "17") (name "Net-(D3-G)") (class "Default")
      (node (ref "D3") (pin "3") (pinfunction "G_3") (pintype "passive"))
      (node (ref "R25") (pin "1") (pinfunction "1_1") (pintype "passive"))
    )
    (net (code "18") (name "Net-(D3-R)") (class "Default")
      (node (ref "D3") (pin "2") (pinfunction "R_2") (pintype "passive"))
      (node (ref "R24") (pin "1") (pinfunction "1_1") (pintype "passive"))
    )
    (net (code "19") (name "Net-(E1-K)") (class "Default")
      (node (ref "C10") (pin "1") (pinfunction "1_1") (pintype "passive"))
      (node (ref "C4") (pin "1") (pinfunction "1_1") (pintype "passive"))
      (node (ref "C6") (pin "2") (pinfunction "2_2") (pintype "passive"))
      (node (ref "C9") (pin "1") (pinfunction "1_1") (pintype "passive"))
      (node (ref "E1") (pin "2") (pinfunction "K_2") (pintype "passive"))
      (node (ref "R9") (pin "1") (pinfunction "1_1") (pintype "passive"))
      (node (ref "V1") (pin "1") (pinfunction "GND_1") (pintype "passive"))
    )
    (net (code "20") (name "Net-(F1-Pad2)") (class "Default")
      (node (ref "F1") (pin "2") (pinfunction "2_2") (pintype "passive"))
      (node (ref "R1") (pin "1") (pinfunction "1_1") (pintype "passive"))
    )
    (net (code "21") (name "Net-(J1-Pad3)") (class "Default")
      (node (ref "J1") (pin "3") (pinfunction "3_3") (pintype "passive"))
      (node (ref "R17") (pin "2") (pinfunction "2_2") (pintype "passive"))
    )
    (net (code "22") (name "Net-(J1-Pad4)") (class "Default")
      (node (ref "J1") (pin "4") (pinfunction "4_4") (pintype "passive"))
      (node (ref "R18") (pin "1") (pinfunction "1_1") (pintype "passive"))
    )
    (net (code "23") (name "Net-(JP1-Pad1)") (class "Default")
      (node (ref "JP1") (pin "1") (pinfunction "1_1") (pintype "passive"))
      (node (ref "R5") (pin "2") (pinfunction "2_2") (pintype "passive"))
    )
    (net (code "24") (name "Net-(JP1-Pad2)") (class "Default")
      (node (ref "JP1") (pin "2") (pinfunction "2_2") (pintype "passive"))
      (node (ref "R7") (pin "2") (pinfunction "2_2") (pintype "passive"))
    )
    (net (code "25") (name "Net-(L1-Pad1)") (class "Default")
      (node (ref "L1") (pin "1") (pinfunction "1_1") (pintype "passive"))
      (node (ref "R1") (pin "2") (pinfunction "2_2") (pintype "passive"))
      (node (ref "RV1") (pin "2") (pinfunction "2_2") (pintype "passive"))
    )
    (net (code "26") (name "Net-(P1-Pad1)") (class "Default")
      (node (ref "P1") (pin "1") (pinfunction "1_1") (pintype "power_in"))
      (node (ref "R12") (pin "2") (pinfunction "2_2") (pintype "passive"))
    )
    (net (code "27") (name "Net-(P1-Pad2)") (class "Default")
      (node (ref "P1") (pin "2") (pinfunction "2_2") (pintype "power_in"))
      (node (ref "R13") (pin "2") (pinfunction "2_2") (pintype "passive"))
    )
    (net (code "28") (name "Net-(P1-Pad3)") (class "Default")
      (node (ref "P1") (pin "3") (pinfunction "3_3") (pintype "power_in"))
      (node (ref "R15") (pin "2") (pinfunction "2_2") (pintype "passive"))
    )
    (net (code "29") (name "Net-(P1-Pad7)") (class "Default")
      (node (ref "P1") (pin "7") (pinfunction "7_7") (pintype "power_in"))
      (node (ref "T1") (pin "3") (pinfunction "3_3") (pintype "passive"))
    )
    (net (code "30") (name "Net-(P1-Pad8)") (class "Default")
      (node (ref "P1") (pin "8") (pinfunction "8_8") (pintype "power_in"))
      (node (ref "T1") (pin "4") (pinfunction "4_4") (pintype "passive"))
    )
    (net (code "31") (name "Net-(P1-Pad9)") (class "Default")
      (node (ref "P1") (pin "9") (pinfunction "9_9") (pintype "power_in"))
      (node (ref "T1") (pin "2") (pinfunction "2_2") (pintype "passive"))
    )
    (net (code "32") (name "Net-(P1-Pad10)") (class "Default")
      (node (ref "P1") (pin "10") (pinfunction "10_10") (pintype "power_in"))
      (node (ref "T1") (pin "1") (pinfunction "1_1") (pintype "passive"))
    )
    (net (code "33") (name "Net-(R28-Pad1)") (class "Default")
      (node (ref "R28") (pin "1") (pinfunction "1_1") (pintype "passive"))
      (node (ref "U3") (pin "143") (pinfunction "VSS_143") (pintype "passive"))
      (node (ref "U3") (pin "71") (pinfunction "VSS_71") (pintype "passive"))
    )
    (net (code "34") (name "Net-(SW2-A1)") (class "Default")
      (node (ref "C16") (pin "1") (pinfunction "1_1") (pintype "passive"))
      (node (ref "R16") (pin "2") (pinfunction "2_2") (pintype "passive"))
      (node (ref "R21") (pin "2") (pinfunction "2_2") (pintype "passive"))
      (node (ref "SW2") (pin "1") (pinfunction "A1_1") (pintype "passive"))
      (node (ref "SW2") (pin "2") (pinfunction "A2_2") (pintype "passive"))
      (node (ref "Z2") (pin "2") (pinfunction "2_2") (pintype "passive"))
    )
    (net (code "35") (name "Net-(U1-L)") (class "Default")
      (node (ref "L4") (pin "2") (pinfunction "2_2") (pintype "passive"))
      (node (ref "U1") (pin "1") (pinfunction "L_1") (pintype "passive"))
    )
    (net (code "36") (name "Net-(U1-N)") (class "Default")
      (node (ref "L4") (pin "3") (pinfunction "3_3") (pintype "passive"))
      (node (ref "U1") (pin "2") (pinfunction "N_2") (pintype "passive"))
    )
    (net (code "37") (name "Net-(U2-A)") (class "Default")
      (node (ref "R2") (pin "1") (pinfunction "1_1") (pintype "passive"))
      (node (ref "R3") (pin "1") (pinfunction "1_1") (pintype "passive"))
      (node (ref "R7") (pin "1") (pinfunction "1_1") (pintype "passive"))
      (node (ref "U2") (pin "6") (pinfunction "A_6") (pintype "passive"))
    )
    (net (code "38") (name "Net-(U2-B)") (class "Default")
      (node (ref "R3") (pin "2") (pinfunction "2_2") (pintype "passive"))
      (node (ref "R5") (pin "1") (pinfunction "1_1") (pintype "passive"))
      (node (ref "R8") (pin "2") (pinfunction "2_2") (pintype "passive"))
      (node (ref "U2") (pin "7") (pinfunction "B_7") (pintype "passive"))
    )
    (net (code "39") (name "Net-(U2-DI)") (class "Default")
      (node (ref "R6") (pin "2") (pinfunction "2_2") (pintype "passive"))
      (node (ref "U2") (pin "4") (pinfunction "DI_4") (pintype "passive"))
    )
    (net (code "40") (name "Net-(U2-RO)") (class "Default")
      (node (ref "R4") (pin "2") (pinfunction "2_2") (pintype "passive"))
      (node (ref "U2") (pin "1") (pinfunction "RO_1") (pintype "passive"))
    )
    (net (code "41") (name "Net-(U3-OSC_IN)") (class "Default")
      (node (ref "C19") (pin "2") (pinfunction "2_2") (pintype "passive"))
      (node (ref "R29") (pin "2") (pinfunction "2_2") (pintype "passive"))
      (node (ref "U3") (pin "23") (pinfunction "OSC_IN_23") (pintype "passive"))
      (node (ref "X2") (pin "1") (pinfunction "1_1") (pintype "passive"))
    )
    (net (code "42") (name "Net-(U3-OSC_OUT)") (class "Default")
      (node (ref "C20") (pin "2") (pinfunction "2_2") (pintype "passive"))
      (node (ref "R29") (pin "1") (pinfunction "1_1") (pintype "passive"))
      (node (ref "U3") (pin "24") (pinfunction "OSC_OUT_24") (pintype "passive"))
      (node (ref "X2") (pin "2") (pinfunction "2_2") (pintype "passive"))
    )
    (net (code "43") (name "Net-(U3-PC14-OSC32_IN)") (class "Default")
      (node (ref "C17") (pin "2") (pinfunction "2_2") (pintype "passive"))
      (node (ref "U3") (pin "8") (pinfunction "PC14-OSC32_IN_8") (pintype "passive"))
      (node (ref "X1") (pin "2") (pinfunction "2_2") (pintype "passive"))
    )
    (net (code "44") (name "Net-(U3-PC15-OSC32_OUT)") (class "Default")
      (node (ref "C18") (pin "2") (pinfunction "2_2") (pintype "passive"))
      (node (ref "U3") (pin "9") (pinfunction "PC15-OSC32_OUT_9") (pintype "passive"))
      (node (ref "X1") (pin "1") (pinfunction "1_1") (pintype "passive"))
    )
    (net (code "45") (name "Net-(U3-Vref+)") (class "Default")
      (node (ref "L7") (pin "2") (pinfunction "2_2") (pintype "passive"))
      (node (ref "U3") (pin "32") (pinfunction "Vref+_32") (pintype "passive"))
    )
    (net (code "46") (name "PA0{slash}WKUP") (class "Default")
      (node (ref "R16") (pin "1") (pinfunction "1_1") (pintype "passive"))
      (node (ref "U3") (pin "34") (pinfunction "PA0-WKUP/USART2_CTS/ADC123_IN0/TIM5_CH1/TIM2_CH1_ETR/TIM8_ETR_34") (pintype "passive"))
    )
    (net (code "47") (name "PA2") (class "Default")
      (node (ref "R6") (pin "1") (pinfunction "1_1") (pintype "passive"))
      (node (ref "U3") (pin "36") (pinfunction "PA2/USART2_TX/ADC123_IN2/TIM5_CH3/TIM2_CH3_36") (pintype "passive"))
    )
    (net (code "48") (name "PA3") (class "Default")
      (node (ref "R4") (pin "1") (pinfunction "1_1") (pintype "passive"))
      (node (ref "U3") (pin "37") (pinfunction "PA3/USART2_RX/ADC123_IN3/TIM5_CH4/TIM2_CH4_37") (pintype "passive"))
    )
    (net (code "49") (name "PA4") (class "Default")
      (node (ref "R14") (pin "2") (pinfunction "2_2") (pintype "passive"))
      (node (ref "U3") (pin "40") (pinfunction "PA4/SPI1_NSS/DAC_OUT1/USART2_CK/ADC12_IN4_40") (pintype "passive"))
      (node (ref "U4") (pin "1") (pinfunction "~{CE}_1") (pintype "passive"))
    )
    (net (code "50") (name "PA5") (class "Default")
      (node (ref "U3") (pin "41") (pinfunction "PA5/SPI1_SCK/DAC_OUT2/ADC12_IN5_41") (pintype "passive"))
      (node (ref "U4") (pin "6") (pinfunction "SCK_6") (pintype "passive"))
    )
    (net (code "51") (name "PA6") (class "Default")
      (node (ref "U3") (pin "42") (pinfunction "PA6/SPI1_MISO/TIM8_BKIN/ADC12_IN6/TIM3_CH1_42") (pintype "passive"))
      (node (ref "U4") (pin "2") (pinfunction "SO_IO1_2") (pintype "passive"))
    )
    (net (code "52") (name "PA7") (class "Default")
      (node (ref "U3") (pin "43") (pinfunction "PA7/SPI1_MOSI/TIM8_CH1N/ADC12_IN7/TIM3_CH2_43") (pintype "passive"))
      (node (ref "U4") (pin "5") (pinfunction "SI_IO0_5") (pintype "passive"))
    )
    (net (code "53") (name "PA9") (class "Default")
      (node (ref "R13") (pin "1") (pinfunction "1_1") (pintype "passive"))
      (node (ref "U3") (pin "101") (pinfunction "PA9/USART1_TX/TIM1_CH2_101") (pintype "passive"))
    )
    (net (code "54") (name "PA10") (class "Default")
      (node (ref "R15") (pin "1") (pinfunction "1_1") (pintype "passive"))
      (node (ref "U3") (pin "102") (pinfunction "PA10/USART1_RX/TIM1_CH3_102") (pintype "passive"))
    )
    (net (code "55") (name "PA13") (class "Default")
      (node (ref "J3") (pin "4") (pinfunction "TMS_4") (pintype "passive"))
      (node (ref "U3") (pin "105") (pinfunction "PA13/JTMS_SWDIO_105") (pintype "passive"))
    )
    (net (code "56") (name "PA14") (class "Default")
      (node (ref "J3") (pin "2") (pinfunction "TCK_2") (pintype "passive"))
      (node (ref "U3") (pin "109") (pinfunction "PA14/JTCK_SWCLK_109") (pintype "passive"))
    )
    (net (code "57") (name "PB0") (class "Default")
      (node (ref "R25") (pin "2") (pinfunction "2_2") (pintype "passive"))
      (node (ref "U3") (pin "46") (pinfunction "PB0/ADC12_IN8/TIM3_CH3/TIM8_CH2N_46") (pintype "passive"))
    )
    (net (code "58") (name "PB1") (class "Default")
      (node (ref "R26") (pin "1") (pinfunction "1_1") (pintype "passive"))
      (node (ref "U3") (pin "47") (pinfunction "PB1/ADC12_IN9/TIM3_CH4/TIM8_CH3N_47") (pintype "passive"))
    )
    (net (code "59") (name "PB5") (class "Default")
      (node (ref "R24") (pin "2") (pinfunction "2_2") (pintype "passive"))
      (node (ref "U3") (pin "135") (pinfunction "PB5/I2C1_SMBAI/SPI3_MOSI/I2S3_SD_135") (pintype "passive"))
    )
    (net (code "60") (name "PB6") (class "Default")
      (node (ref "R19") (pin "2") (pinfunction "2_2") (pintype "passive"))
      (node (ref "U3") (pin "136") (pinfunction "PB6/I2C1_SCL/TIM4_CH1_136") (pintype "passive"))
      (node (ref "U5") (pin "6") (pinfunction "SCL_6") (pintype "passive"))
    )
    (net (code "61") (name "PB7") (class "Default")
      (node (ref "R20") (pin "2") (pinfunction "2_2") (pintype "passive"))
      (node (ref "U3") (pin "137") (pinfunction "PB7/I2C1_SDA/FSMC_NADV/TIM4_CH2_137") (pintype "passive"))
      (node (ref "U5") (pin "5") (pinfunction "SDA_5") (pintype "passive"))
    )
    (net (code "62") (name "PB10") (class "Default")
      (node (ref "JP3") (pin "4") (pinfunction "4_4") (pintype "passive"))
      (node (ref "U3") (pin "69") (pinfunction "PB10/I2C2_SCL/USART3_TX_69") (pintype "passive"))
    )
    (net (code "63") (name "PB11") (class "Default")
      (node (ref "JP3") (pin "6") (pinfunction "6_6") (pintype "passive"))
      (node (ref "U3") (pin "70") (pinfunction "PB11/I2C2_SDA/USART3_RX_70") (pintype "passive"))
    )
    (net (code "64") (name "PC10") (class "Default")
      (node (ref "JP3") (pin "3") (pinfunction "3_3") (pintype "passive"))
      (node (ref "U3") (pin "111") (pinfunction "PC10/UART4_TX/SDIO_D2_111") (pintype "passive"))
    )
    (net (code "65") (name "PC11") (class "Default")
      (node (ref "JP3") (pin "5") (pinfunction "5_5") (pintype "passive"))
      (node (ref "U3") (pin "112") (pinfunction "PC11/UART4_RX/SDIO_D3_112") (pintype "passive"))
    )
    (net (code "66") (name "PD0") (class "Default")
      (node (ref "J2") (pin "16") (pinfunction "FSMC_D02_16") (pintype "passive"))
      (node (ref "U3") (pin "114") (pinfunction "PD0/FSMC_D2_114") (pintype "passive"))
    )
    (net (code "67") (name "PD1") (class "Default")
      (node (ref "J2") (pin "15") (pinfunction "FSMC_D03_15") (pintype "passive"))
      (node (ref "U3") (pin "115") (pinfunction "PD1/FSMC_D3_115") (pintype "passive"))
    )
    (net (code "68") (name "PD4") (class "Default")
      (node (ref "J2") (pin "19") (pinfunction "FSMC_NOE_19") (pintype "passive"))
      (node (ref "U3") (pin "118") (pinfunction "PD4/FSMC_NOE_118") (pintype "passive"))
    )
    (net (code "69") (name "PD5") (class "Default")
      (node (ref "J2") (pin "20") (pinfunction "FSMC_NWE_20") (pintype "passive"))
      (node (ref "U3") (pin "119") (pinfunction "PD5/FSMC_NWE_119") (pintype "passive"))
    )
    (net (code "70") (name "PD8") (class "Default")
      (node (ref "J2") (pin "5") (pinfunction "FSMC_D13_5") (pintype "passive"))
      (node (ref "U3") (pin "77") (pinfunction "PD8/FSMC_D13_77") (pintype "passive"))
    )
    (net (code "71") (name "PD9") (class "Default")
      (node (ref "J2") (pin "4") (pinfunction "FSMC_D14_4") (pintype "passive"))
      (node (ref "U3") (pin "78") (pinfunction "PD9/FSMC_D14_78") (pintype "passive"))
    )
    (net (code "72") (name "PD10") (class "Default")
      (node (ref "J2") (pin "3") (pinfunction "FSMC_D15_3") (pintype "passive"))
      (node (ref "U3") (pin "79") (pinfunction "PD10/FSMC_D15_79") (pintype "passive"))
    )
    (net (code "73") (name "PD14") (class "Default")
      (node (ref "J2") (pin "18") (pinfunction "FSMC_D00_18") (pintype "passive"))
      (node (ref "U3") (pin "85") (pinfunction "PD14/FSMC_D0_85") (pintype "passive"))
    )
    (net (code "74") (name "PD15") (class "Default")
      (node (ref "J2") (pin "17") (pinfunction "FSMC_D01_17") (pintype "passive"))
      (node (ref "U3") (pin "86") (pinfunction "PD15/FSMC_D1_86") (pintype "passive"))
    )
    (net (code "75") (name "PE2") (class "Default")
      (node (ref "J2") (pin "21") (pinfunction "FSMC_A23_21") (pintype "passive"))
      (node (ref "U3") (pin "1") (pinfunction "PE2/TRACECK/FSMC_A23_1") (pintype "passive"))
    )
    (net (code "76") (name "PE7") (class "Default")
      (node (ref "J2") (pin "14") (pinfunction "FSMC_D04_14") (pintype "passive"))
      (node (ref "U3") (pin "58") (pinfunction "PE7/FSMC_D4_58") (pintype "passive"))
    )
    (net (code "77") (name "PE8") (class "Default")
      (node (ref "J2") (pin "13") (pinfunction "FSMC_D05_13") (pintype "passive"))
      (node (ref "U3") (pin "59") (pinfunction "PE8/FSMC_D5_59") (pintype "passive"))
    )
    (net (code "78") (name "PE9") (class "Default")
      (node (ref "J2") (pin "12") (pinfunction "FSMC_D06_12") (pintype "passive"))
      (node (ref "U3") (pin "60") (pinfunction "PE9/FSMC_D6_60") (pintype "passive"))
    )
    (net (code "79") (name "PE10") (class "Default")
      (node (ref "J2") (pin "11") (pinfunction "FSMC_D07_11") (pintype "passive"))
      (node (ref "U3") (pin "63") (pinfunction "PE10/FSMC_D7_63") (pintype "passive"))
    )
    (net (code "80") (name "PE11") (class "Default")
      (node (ref "J2") (pin "10") (pinfunction "FSMC_D08_10") (pintype "passive"))
      (node (ref "U3") (pin "64") (pinfunction "PE11/FSMC_D8_64") (pintype "passive"))
    )
    (net (code "81") (name "PE12") (class "Default")
      (node (ref "J2") (pin "9") (pinfunction "FSMC_D09_9") (pintype "passive"))
      (node (ref "U3") (pin "65") (pinfunction "PE12/FSMC_D9_65") (pintype "passive"))
    )
    (net (code "82") (name "PE13") (class "Default")
      (node (ref "J2") (pin "8") (pinfunction "FSMC_D10_8") (pintype "passive"))
      (node (ref "U3") (pin "66") (pinfunction "PE13/FSMC_D10_66") (pintype "passive"))
    )
    (net (code "83") (name "PE14") (class "Default")
      (node (ref "J2") (pin "7") (pinfunction "FSMC_D11_7") (pintype "passive"))
      (node (ref "U3") (pin "67") (pinfunction "PE14/FSMC_D11_67") (pintype "passive"))
    )
    (net (code "84") (name "PE15") (class "Default")
      (node (ref "J2") (pin "6") (pinfunction "FSMC_D12_6") (pintype "passive"))
      (node (ref "U3") (pin "68") (pinfunction "PE15/FSMC_D12_68") (pintype "passive"))
    )
    (net (code "85") (name "PF6") (class "Default")
      (node (ref "J2") (pin "26") (pinfunction "CPT_IO26_26") (pintype "passive"))
      (node (ref "U3") (pin "18") (pinfunction "PF6/ADC3_IN4/FSMC_NIORD_18") (pintype "passive"))
    )
    (net (code "86") (name "PF9") (class "Default")
      (node (ref "J2") (pin "27") (pinfunction "CPT_IO27_27") (pintype "passive"))
      (node (ref "U3") (pin "21") (pinfunction "PF9/ADC3_IN7/FSMC_CD_21") (pintype "passive"))
    )
    (net (code "87") (name "PF10") (class "Default")
      (node (ref "J2") (pin "24") (pinfunction "CPT_IO24_24") (pintype "passive"))
      (node (ref "U3") (pin "22") (pinfunction "PF10/ADC3_IN8/FSMC_INTR_22") (pintype "passive"))
    )
    (net (code "88") (name "PF11") (class "Default")
      (node (ref "J2") (pin "25") (pinfunction "CPT_IO25_25") (pintype "passive"))
      (node (ref "U3") (pin "49") (pinfunction "PF11/FSMC_NIOS16_49") (pintype "passive"))
    )
    (net (code "89") (name "PG6") (class "Default")
      (node (ref "J2") (pin "28") (pinfunction "LCD_BL_28") (pintype "passive"))
      (node (ref "U3") (pin "91") (pinfunction "PG6/FSMC_INT2_91") (pintype "passive"))
    )
    (net (code "90") (name "PG7") (class "Default")
      (node (ref "J2") (pin "23") (pinfunction "CPT_IO23_23") (pintype "passive"))
      (node (ref "U3") (pin "92") (pinfunction "PG7/FSMC_INT3_92") (pintype "passive"))
    )
    (net (code "91") (name "PG11") (class "Default")
      (node (ref "J2") (pin "2") (pinfunction "LCD_RST_2") (pintype "passive"))
      (node (ref "U3") (pin "126") (pinfunction "PG11/FSMC_NCE4_2_126") (pintype "passive"))
    )
    (net (code "92") (name "PG12") (class "Default")
      (node (ref "J2") (pin "22") (pinfunction "FSMC_NE4_22") (pintype "passive"))
      (node (ref "U3") (pin "127") (pinfunction "PG12/FSMC_NE4_127") (pintype "passive"))
    )
    (net (code "93") (name "VA") (class "Default")
      (node (ref "C14") (pin "1") (pinfunction "1_1") (pintype "passive"))
      (node (ref "F1") (pin "1") (pinfunction "1_1") (pintype "passive"))
      (node (ref "JP2") (pin "1") (pinfunction "1_1") (pintype "passive"))
    )
    (net (code "94") (name "VN") (class "Default")
      (node (ref "JP2") (pin "2") (pinfunction "2_2") (pintype "passive"))
      (node (ref "L6") (pin "1") (pinfunction "1_1") (pintype "passive"))
      (node (ref "RV1") (pin "1") (pinfunction "1_1") (pintype "passive"))
      (node (ref "T1") (pin "6") (pinfunction "6_6") (pintype "passive"))
    )
    (net (code "95") (name "unconnected-(IC1-GND-Pad6)") (class "Default")
      (node (ref "IC1") (pin "6") (pinfunction "GND_6") (pintype "power_in+no_connect"))
    )
    (net (code "96") (name "unconnected-(U3-NC-Pad106)") (class "Default")
      (node (ref "U3") (pin "106") (pinfunction "NC_106") (pintype "passive+no_connect"))
    )
    (net (code "97") (name "unconnected-(U3-PA1{slash}USART2_RTS{slash}ADC123_IN1{slash}TIM5_CH2{slash}TIM2_CH2-Pad35)") (class "Default")
      (node (ref "U3") (pin "35") (pinfunction "PA1/USART2_RTS/ADC123_IN1/TIM5_CH2/TIM2_CH2_35") (pintype "passive+no_connect"))
    )
    (net (code "98") (name "unconnected-(U3-PA8{slash}USART1_CK{slash}TIM1_CH1{slash}MCO-Pad100)") (class "Default")
      (node (ref "U3") (pin "100") (pinfunction "PA8/USART1_CK/TIM1_CH1/MCO_100") (pintype "passive+no_connect"))
    )
    (net (code "99") (name "unconnected-(U3-PA11{slash}USART1_CTS{slash}CAN_RX{slash}TIM1_CH4{slash}USBDM-Pad103)") (class "Default")
      (node (ref "U3") (pin "103") (pinfunction "PA11/USART1_CTS/CAN_RX/TIM1_CH4/USBDM_103") (pintype "passive+no_connect"))
    )
    (net (code "100") (name "unconnected-(U3-PA12{slash}USART1_RTS{slash}CAN_TX{slash}TIM1_ETR{slash}USBDP-Pad104)") (class "Default")
      (node (ref "U3") (pin "104") (pinfunction "PA12/USART1_RTS/CAN_TX/TIM1_ETR/USBDP_104") (pintype "passive+no_connect"))
    )
    (net (code "101") (name "unconnected-(U3-PA15{slash}JTDI{slash}SPI3_NSS{slash}I2S3_WS-Pad110)") (class "Default")
      (node (ref "U3") (pin "110") (pinfunction "PA15/JTDI/SPI3_NSS/I2S3_WS_110") (pintype "passive+no_connect"))
    )
    (net (code "102") (name "unconnected-(U3-PB3{slash}JTDO{slash}TRACESWO{slash}SPI3_SCK{slash}I2S3_CK-Pad133)") (class "Default")
      (node (ref "U3") (pin "133") (pinfunction "PB3/JTDO/TRACESWO/SPI3_SCK/I2S3_CK_133") (pintype "passive+no_connect"))
    )
    (net (code "103") (name "unconnected-(U3-PB4{slash}JNTRST{slash}SPI3_MISO-Pad134)") (class "Default")
      (node (ref "U3") (pin "134") (pinfunction "PB4/JNTRST/SPI3_MISO_134") (pintype "passive+no_connect"))
    )
    (net (code "104") (name "unconnected-(U3-PB8{slash}TIM4_CH3{slash}SDIO_D4-Pad139)") (class "Default")
      (node (ref "U3") (pin "139") (pinfunction "PB8/TIM4_CH3/SDIO_D4_139") (pintype "passive+no_connect"))
    )
    (net (code "105") (name "unconnected-(U3-PB9{slash}TIM4_CH4{slash}SDIO_D5-Pad140)") (class "Default")
      (node (ref "U3") (pin "140") (pinfunction "PB9/TIM4_CH4/SDIO_D5_140") (pintype "passive+no_connect"))
    )
    (net (code "106") (name "unconnected-(U3-PB12{slash}SPI2_NSS{slash}I2S2_WS{slash}I2C2_SMBAI{slash}USART3_CK{slash}TIM1BKIN-Pad73)") (class "Default")
      (node (ref "U3") (pin "73") (pinfunction "PB12/SPI2_NSS/I2S2_WS/I2C2_SMBAI/USART3_CK/TIM1BKIN_73") (pintype "passive+no_connect"))
    )
    (net (code "107") (name "unconnected-(U3-PB13{slash}SPI2_SCK{slash}I2S2_CK{slash}USART3_CTS{slash}TIM1_CH1N-Pad74)") (class "Default")
      (node (ref "U3") (pin "74") (pinfunction "PB13/SPI2_SCK/I2S2_CK/USART3_CTS/TIM1_CH1N_74") (pintype "passive+no_connect"))
    )
    (net (code "108") (name "unconnected-(U3-PB14{slash}SPI2_MISO{slash}USART3_RTS{slash}TIM1_CH2N-Pad75)") (class "Default")
      (node (ref "U3") (pin "75") (pinfunction "PB14/SPI2_MISO/USART3_RTS/TIM1_CH2N_75") (pintype "passive+no_connect"))
    )
    (net (code "109") (name "unconnected-(U3-PB15{slash}SPI2_MOSI{slash}I2S2_SD{slash}TIM1_CH3N-Pad76)") (class "Default")
      (node (ref "U3") (pin "76") (pinfunction "PB15/SPI2_MOSI/I2S2_SD/TIM1_CH3N_76") (pintype "passive+no_connect"))
    )
    (net (code "110") (name "unconnected-(U3-PC0{slash}ADC123_IN10-Pad26)") (class "Default")
      (node (ref "U3") (pin "26") (pinfunction "PC0/ADC123_IN10_26") (pintype "passive+no_connect"))
    )
    (net (code "111") (name "unconnected-(U3-PC1{slash}ADC123_IN11-Pad27)") (class "Default")
      (node (ref "U3") (pin "27") (pinfunction "PC1/ADC123_IN11_27") (pintype "passive+no_connect"))
    )
    (net (code "112") (name "unconnected-(U3-PC2{slash}ADC123_IN12-Pad28)") (class "Default")
      (node (ref "U3") (pin "28") (pinfunction "PC2/ADC123_IN12_28") (pintype "passive+no_connect"))
    )
    (net (code "113") (name "unconnected-(U3-PC3{slash}ADC123_IN13-Pad29)") (class "Default")
      (node (ref "U3") (pin "29") (pinfunction "PC3/ADC123_IN13_29") (pintype "passive+no_connect"))
    )
    (net (code "114") (name "unconnected-(U3-PC4{slash}ADC12_IN14-Pad44)") (class "Default")
      (node (ref "U3") (pin "44") (pinfunction "PC4/ADC12_IN14_44") (pintype "passive+no_connect"))
    )
    (net (code "115") (name "unconnected-(U3-PC5{slash}ADC12_IN15-Pad45)") (class "Default")
      (node (ref "U3") (pin "45") (pinfunction "PC5/ADC12_IN15_45") (pintype "passive+no_connect"))
    )
    (net (code "116") (name "unconnected-(U3-PC6{slash}I2S2_MCK{slash}TIM8_CH1{slash}SDIO_D6-Pad96)") (class "Default")
      (node (ref "U3") (pin "96") (pinfunction "PC6/I2S2_MCK/TIM8_CH1/SDIO_D6_96") (pintype "passive+no_connect"))
    )
    (net (code "117") (name "unconnected-(U3-PC7{slash}I2S3_MCK{slash}TIM8_CH2{slash}SDIO_D7-Pad97)") (class "Default")
      (node (ref "U3") (pin "97") (pinfunction "PC7/I2S3_MCK/TIM8_CH2/SDIO_D7_97") (pintype "passive+no_connect"))
    )
    (net (code "118") (name "unconnected-(U3-PC8{slash}TIM8_CH3{slash}SDIO_D0-Pad98)") (class "Default")
      (node (ref "U3") (pin "98") (pinfunction "PC8/TIM8_CH3/SDIO_D0_98") (pintype "passive+no_connect"))
    )
    (net (code "119") (name "unconnected-(U3-PC9{slash}TIM8_CH4{slash}SDIO_D1-Pad99)") (class "Default")
      (node (ref "U3") (pin "99") (pinfunction "PC9/TIM8_CH4/SDIO_D1_99") (pintype "passive+no_connect"))
    )
    (net (code "120") (name "unconnected-(U3-PC12{slash}UART5_TX{slash}SDIO_CK-Pad113)") (class "Default")
      (node (ref "U3") (pin "113") (pinfunction "PC12/UART5_TX/SDIO_CK_113") (pintype "passive+no_connect"))
    )
    (net (code "121") (name "unconnected-(U3-PC13-TAMPER-RTC-Pad7)") (class "Default")
      (node (ref "U3") (pin "7") (pinfunction "PC13-TAMPER-RTC_7") (pintype "passive+no_connect"))
    )
    (net (code "122") (name "unconnected-(U3-PD2{slash}TIM3_ETR{slash}UART5_RX{slash}SDIO_CMD-Pad116)") (class "Default")
      (node (ref "U3") (pin "116") (pinfunction "PD2/TIM3_ETR/UART5_RX/SDIO_CMD_116") (pintype "passive+no_connect"))
    )
    (net (code "123") (name "unconnected-(U3-PD3{slash}FSMC_CLK-Pad117)") (class "Default")
      (node (ref "U3") (pin "117") (pinfunction "PD3/FSMC_CLK_117") (pintype "passive+no_connect"))
    )
    (net (code "124") (name "unconnected-(U3-PD6{slash}FSMC_NWAIT-Pad122)") (class "Default")
      (node (ref "U3") (pin "122") (pinfunction "PD6/FSMC_NWAIT_122") (pintype "passive+no_connect"))
    )
    (net (code "125") (name "unconnected-(U3-PD7{slash}FSMC_NE1{slash}FSMC_NCE2-Pad123)") (class "Default")
      (node (ref "U3") (pin "123") (pinfunction "PD7/FSMC_NE1/FSMC_NCE2_123") (pintype "passive+no_connect"))
    )
    (net (code "126") (name "unconnected-(U3-PD11{slash}FSMC_A16-Pad80)") (class "Default")
      (node (ref "U3") (pin "80") (pinfunction "PD11/FSMC_A16_80") (pintype "passive+no_connect"))
    )
    (net (code "127") (name "unconnected-(U3-PD12{slash}FSMC_A17-Pad81)") (class "Default")
      (node (ref "U3") (pin "81") (pinfunction "PD12/FSMC_A17_81") (pintype "passive+no_connect"))
    )
    (net (code "128") (name "unconnected-(U3-PD13{slash}FSMC_A18-Pad82)") (class "Default")
      (node (ref "U3") (pin "82") (pinfunction "PD13/FSMC_A18_82") (pintype "passive+no_connect"))
    )
    (net (code "129") (name "unconnected-(U3-PE0{slash}TIM4_ETR{slash}FSMC_NBL0-Pad141)") (class "Default")
      (node (ref "U3") (pin "141") (pinfunction "PE0/TIM4_ETR/FSMC_NBL0_141") (pintype "passive+no_connect"))
    )
    (net (code "130") (name "unconnected-(U3-PE1{slash}FSMC_NBL1-Pad142)") (class "Default")
      (node (ref "U3") (pin "142") (pinfunction "PE1/FSMC_NBL1_142") (pintype "passive+no_connect"))
    )
    (net (code "131") (name "unconnected-(U3-PE3{slash}TRACED0{slash}FSMC_A19-Pad2)") (class "Default")
      (node (ref "U3") (pin "2") (pinfunction "PE3/TRACED0/FSMC_A19_2") (pintype "passive+no_connect"))
    )
    (net (code "132") (name "unconnected-(U3-PE4{slash}TRACED1{slash}FSMC_A20-Pad3)") (class "Default")
      (node (ref "U3") (pin "3") (pinfunction "PE4/TRACED1/FSMC_A20_3") (pintype "passive+no_connect"))
    )
    (net (code "133") (name "unconnected-(U3-PE5{slash}TRACED2{slash}FSMC_A21-Pad4)") (class "Default")
      (node (ref "U3") (pin "4") (pinfunction "PE5/TRACED2/FSMC_A21_4") (pintype "passive+no_connect"))
    )
    (net (code "134") (name "unconnected-(U3-PE6{slash}TRACED3{slash}FSMC_A22-Pad5)") (class "Default")
      (node (ref "U3") (pin "5") (pinfunction "PE6/TRACED3/FSMC_A22_5") (pintype "passive+no_connect"))
    )
    (net (code "135") (name "unconnected-(U3-PF0{slash}FSMC_A0-Pad10)") (class "Default")
      (node (ref "U3") (pin "10") (pinfunction "PF0/FSMC_A0_10") (pintype "passive+no_connect"))
    )
    (net (code "136") (name "unconnected-(U3-PF1{slash}FSMC_A1-Pad11)") (class "Default")
      (node (ref "U3") (pin "11") (pinfunction "PF1/FSMC_A1_11") (pintype "passive+no_connect"))
    )
    (net (code "137") (name "unconnected-(U3-PF2{slash}FSMC_A2-Pad12)") (class "Default")
      (node (ref "U3") (pin "12") (pinfunction "PF2/FSMC_A2_12") (pintype "passive+no_connect"))
    )
    (net (code "138") (name "unconnected-(U3-PF3{slash}FSMC_A3-Pad13)") (class "Default")
      (node (ref "U3") (pin "13") (pinfunction "PF3/FSMC_A3_13") (pintype "passive+no_connect"))
    )
    (net (code "139") (name "unconnected-(U3-PF4{slash}FSMC_A4-Pad14)") (class "Default")
      (node (ref "U3") (pin "14") (pinfunction "PF4/FSMC_A4_14") (pintype "passive+no_connect"))
    )
    (net (code "140") (name "unconnected-(U3-PF5{slash}FSMC_A5-Pad15)") (class "Default")
      (node (ref "U3") (pin "15") (pinfunction "PF5/FSMC_A5_15") (pintype "passive+no_connect"))
    )
    (net (code "141") (name "unconnected-(U3-PF7{slash}ADC3_IN5{slash}FSMC_NREG-Pad19)") (class "Default")
      (node (ref "U3") (pin "19") (pinfunction "PF7/ADC3_IN5/FSMC_NREG_19") (pintype "passive+no_connect"))
    )
    (net (code "142") (name "unconnected-(U3-PF8{slash}ADC3_IN6{slash}FSMC_NIOWR-Pad20)") (class "Default")
      (node (ref "U3") (pin "20") (pinfunction "PF8/ADC3_IN6/FSMC_NIOWR_20") (pintype "passive+no_connect"))
    )
    (net (code "143") (name "unconnected-(U3-PF12{slash}FSMC_A6-Pad50)") (class "Default")
      (node (ref "U3") (pin "50") (pinfunction "PF12/FSMC_A6_50") (pintype "passive+no_connect"))
    )
    (net (code "144") (name "unconnected-(U3-PF13{slash}FSMC_A7-Pad53)") (class "Default")
      (node (ref "U3") (pin "53") (pinfunction "PF13/FSMC_A7_53") (pintype "passive+no_connect"))
    )
    (net (code "145") (name "unconnected-(U3-PF14{slash}FSMC_A8-Pad54)") (class "Default")
      (node (ref "U3") (pin "54") (pinfunction "PF14/FSMC_A8_54") (pintype "passive+no_connect"))
    )
    (net (code "146") (name "unconnected-(U3-PF15{slash}FSMC_A9-Pad55)") (class "Default")
      (node (ref "U3") (pin "55") (pinfunction "PF15/FSMC_A9_55") (pintype "passive+no_connect"))
    )
    (net (code "147") (name "unconnected-(U3-PG0{slash}FSMC_A10-Pad56)") (class "Default")
      (node (ref "U3") (pin "56") (pinfunction "PG0/FSMC_A10_56") (pintype "passive+no_connect"))
    )
    (net (code "148") (name "unconnected-(U3-PG1{slash}FSMC_A11-Pad57)") (class "Default")
      (node (ref "U3") (pin "57") (pinfunction "PG1/FSMC_A11_57") (pintype "passive+no_connect"))
    )
    (net (code "149") (name "unconnected-(U3-PG2{slash}FSMC_A12-Pad87)") (class "Default")
      (node (ref "U3") (pin "87") (pinfunction "PG2/FSMC_A12_87") (pintype "passive+no_connect"))
    )
    (net (code "150") (name "unconnected-(U3-PG3{slash}FSMC_A13-Pad88)") (class "Default")
      (node (ref "U3") (pin "88") (pinfunction "PG3/FSMC_A13_88") (pintype "passive+no_connect"))
    )
    (net (code "151") (name "unconnected-(U3-PG4{slash}FSMC_A14-Pad89)") (class "Default")
      (node (ref "U3") (pin "89") (pinfunction "PG4/FSMC_A14_89") (pintype "passive+no_connect"))
    )
    (net (code "152") (name "unconnected-(U3-PG5{slash}FSMC_A15-Pad90)") (class "Default")
      (node (ref "U3") (pin "90") (pinfunction "PG5/FSMC_A15_90") (pintype "passive+no_connect"))
    )
    (net (code "153") (name "unconnected-(U3-PG8-Pad93)") (class "Default")
      (node (ref "U3") (pin "93") (pinfunction "PG8_93") (pintype "passive+no_connect"))
    )
    (net (code "154") (name "unconnected-(U3-PG9{slash}FSMC_NE2{slash}FSMC_NCE3-Pad124)") (class "Default")
      (node (ref "U3") (pin "124") (pinfunction "PG9/FSMC_NE2/FSMC_NCE3_124") (pintype "passive+no_connect"))
    )
    (net (code "155") (name "unconnected-(U3-PG10{slash}FSMC_NCE4_1{slash}FSMC_NE3-Pad125)") (class "Default")
      (node (ref "U3") (pin "125") (pinfunction "PG10/FSMC_NCE4_1/FSMC_NE3_125") (pintype "passive+no_connect"))
    )
    (net (code "156") (name "unconnected-(U3-PG13{slash}FSMC_A24-Pad128)") (class "Default")
      (node (ref "U3") (pin "128") (pinfunction "PG13/FSMC_A24_128") (pintype "passive+no_connect"))
    )
    (net (code "157") (name "unconnected-(U3-PG14{slash}FSMC_A25-Pad129)") (class "Default")
      (node (ref "U3") (pin "129") (pinfunction "PG14/FSMC_A25_129") (pintype "passive+no_connect"))
    )
    (net (code "158") (name "unconnected-(U3-PG15-Pad132)") (class "Default")
      (node (ref "U3") (pin "132") (pinfunction "PG15_132") (pintype "passive+no_connect"))
    )
    (net (code "159") (name "unconnected-(V1-Vout-Pad4)") (class "Default")
      (node (ref "V1") (pin "4") (pinfunction "Vout_4") (pintype "passive+no_connect"))
    )
  )
)
